# Power_connector.net
KiCad netlist of a schematic drawn in EAGLE
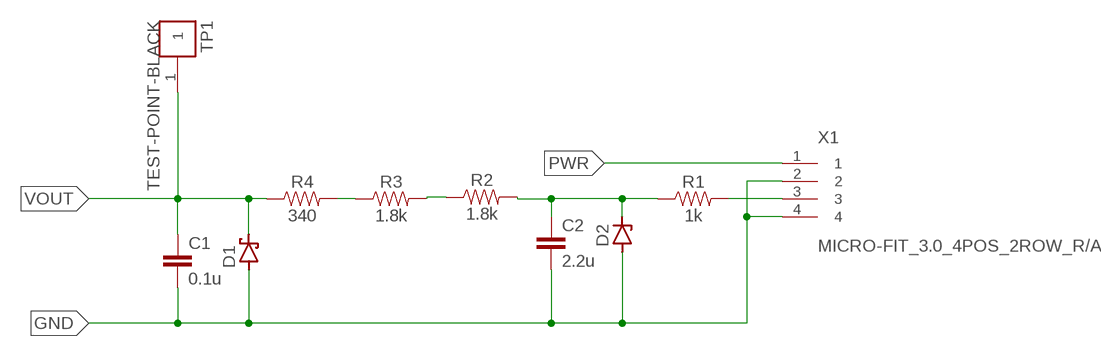
[diagram p0: schematic, sheet 1]

(export (version "E")
  (design (tool "Eeschema 10.0.6"))
  (components
    (comp (ref "C1")
      (value "0.1u")
      (footprint "eagle-import:C0603")
      (fields (field (name "MANUFACTURER") "Murata Electronics"))
      (libsource (lib "eagle-import") (part "CAP-0.1UF-0603-25V-X8R"))
    )
    (comp (ref "C2")
      (value "2.2u")
      (footprint "eagle-import:0603")
      (fields (field (name "MFR") "Murata Electronics") (field (name "MPN") "GCM188R70J225KE22D"))
      (libsource (lib "eagle-import") (part "CAP-2.2UF-10%-6.3V-X7R-0603IPC"))
    )
    (comp (ref "D1")
      (value "SCHOTTKY-DIODESMD")
      (footprint "eagle-import:SMB")
      (libsource (lib "eagle-import") (part "SCHOTTKY-DIODESMD"))
    )
    (comp (ref "D2")
      (value "ZENER-DIODESOT23")
      (footprint "eagle-import:SOT23")
      (libsource (lib "eagle-import") (part "ZENER-DIODESOT23"))
    )
    (comp (ref "R1")
      (value "1k")
      (footprint "eagle-import:R0603")
      (fields (field (name "MANUFACTURER") "Panasonic"))
      (libsource (lib "eagle-import") (part "RES-1KOHM-0603-1/10W-1%"))
    )
    (comp (ref "R2")
      (value "1.8k")
      (footprint "eagle-import:R0603")
      (fields (field (name "MANUFACTURER") "Panasonic"))
      (libsource (lib "eagle-import") (part "RES-1.8KOHM-0603-1/10W-.1%"))
    )
    (comp (ref "R3")
      (value "1.8k")
      (footprint "eagle-import:R0603")
      (fields (field (name "MANUFACTURER") "Panasonic"))
      (libsource (lib "eagle-import") (part "RES-1.8KOHM-0603-1/10W-.1%"))
    )
    (comp (ref "R4")
      (value "340")
      (footprint "eagle-import:R0603")
      (fields (field (name "MANUFACTURER") "Panasonic"))
      (libsource (lib "eagle-import") (part "RES-340OHM-0603-1/10W-1%"))
    )
    (comp (ref "TP1")
      (value "TEST-POINT-BLACK")
      (footprint "eagle-import:KEYSTONE_5001_0")
      (fields (field (name "MANUFACTURER") "Keystone Electronics"))
      (libsource (lib "eagle-import") (part "TEST-POINT-BLACK"))
    )
    (comp (ref "X1")
      (value "MICRO-FIT_3.0_4POS_2ROW_R/A")
      (footprint "eagle-import:0430450400")
      (fields (field (name "MANUFACTURER") "Molex"))
      (libsource (lib "eagle-import") (part "MICRO-FIT_3.0_4POS_2ROW_R/A"))
    )
  )
  (nets
    (net (code "1") (name "GND") (class "Default")
      (node (ref "C1") (pin "2") (pinfunction "2_2") (pintype "passive"))
      (node (ref "C2") (pin "2") (pinfunction "2_2") (pintype "passive"))
      (node (ref "D1") (pin "A") (pinfunction "A_A") (pintype "passive"))
      (node (ref "D2") (pin "1") (pinfunction "A_1") (pintype "passive"))
      (node (ref "X1") (pin "2") (pinfunction "2_2") (pintype "bidirectional"))
      (node (ref "X1") (pin "4") (pinfunction "4_4") (pintype "bidirectional"))
    )
    (net (code "2") (name "Net-(D2-C)") (class "Default")
      (node (ref "C2") (pin "1") (pinfunction "1_1") (pintype "passive"))
      (node (ref "D2") (pin "3") (pinfunction "C_3") (pintype "passive"))
      (node (ref "R1") (pin "1") (pinfunction "1_1") (pintype "passive"))
      (node (ref "R2") (pin "2") (pinfunction "2_2") (pintype "passive"))
    )
    (net (code "3") (name "Net-(R1-Pad2)") (class "Default")
      (node (ref "R1") (pin "2") (pinfunction "2_2") (pintype "passive"))
      (node (ref "X1") (pin "3") (pinfunction "3_3") (pintype "bidirectional"))
    )
    (net (code "4") (name "Net-(R2-Pad1)") (class "Default")
      (node (ref "R2") (pin "1") (pinfunction "1_1") (pintype "passive"))
      (node (ref "R3") (pin "2") (pinfunction "2_2") (pintype "passive"))
    )
    (net (code "5") (name "Net-(R3-Pad1)") (class "Default")
      (node (ref "R3") (pin "1") (pinfunction "1_1") (pintype "passive"))
      (node (ref "R4") (pin "2") (pinfunction "2_2") (pintype "passive"))
    )
    (net (code "6") (name "PWR") (class "Default")
      (node (ref "X1") (pin "1") (pinfunction "1_1") (pintype "bidirectional"))
    )
    (net (code "7") (name "VOUT") (class "Default")
      (node (ref "C1") (pin "1") (pinfunction "1_1") (pintype "passive"))
      (node (ref "D1") (pin "C") (pinfunction "C_C") (pintype "passive"))
      (node (ref "R4") (pin "1") (pinfunction "1_1") (pintype "passive"))
      (node (ref "TP1") (pin "1") (pinfunction "1_1") (pintype "bidirectional"))
    )
  )
)
